# interface_gate.net
KiCad netlist of a schematic drawn in EAGLE
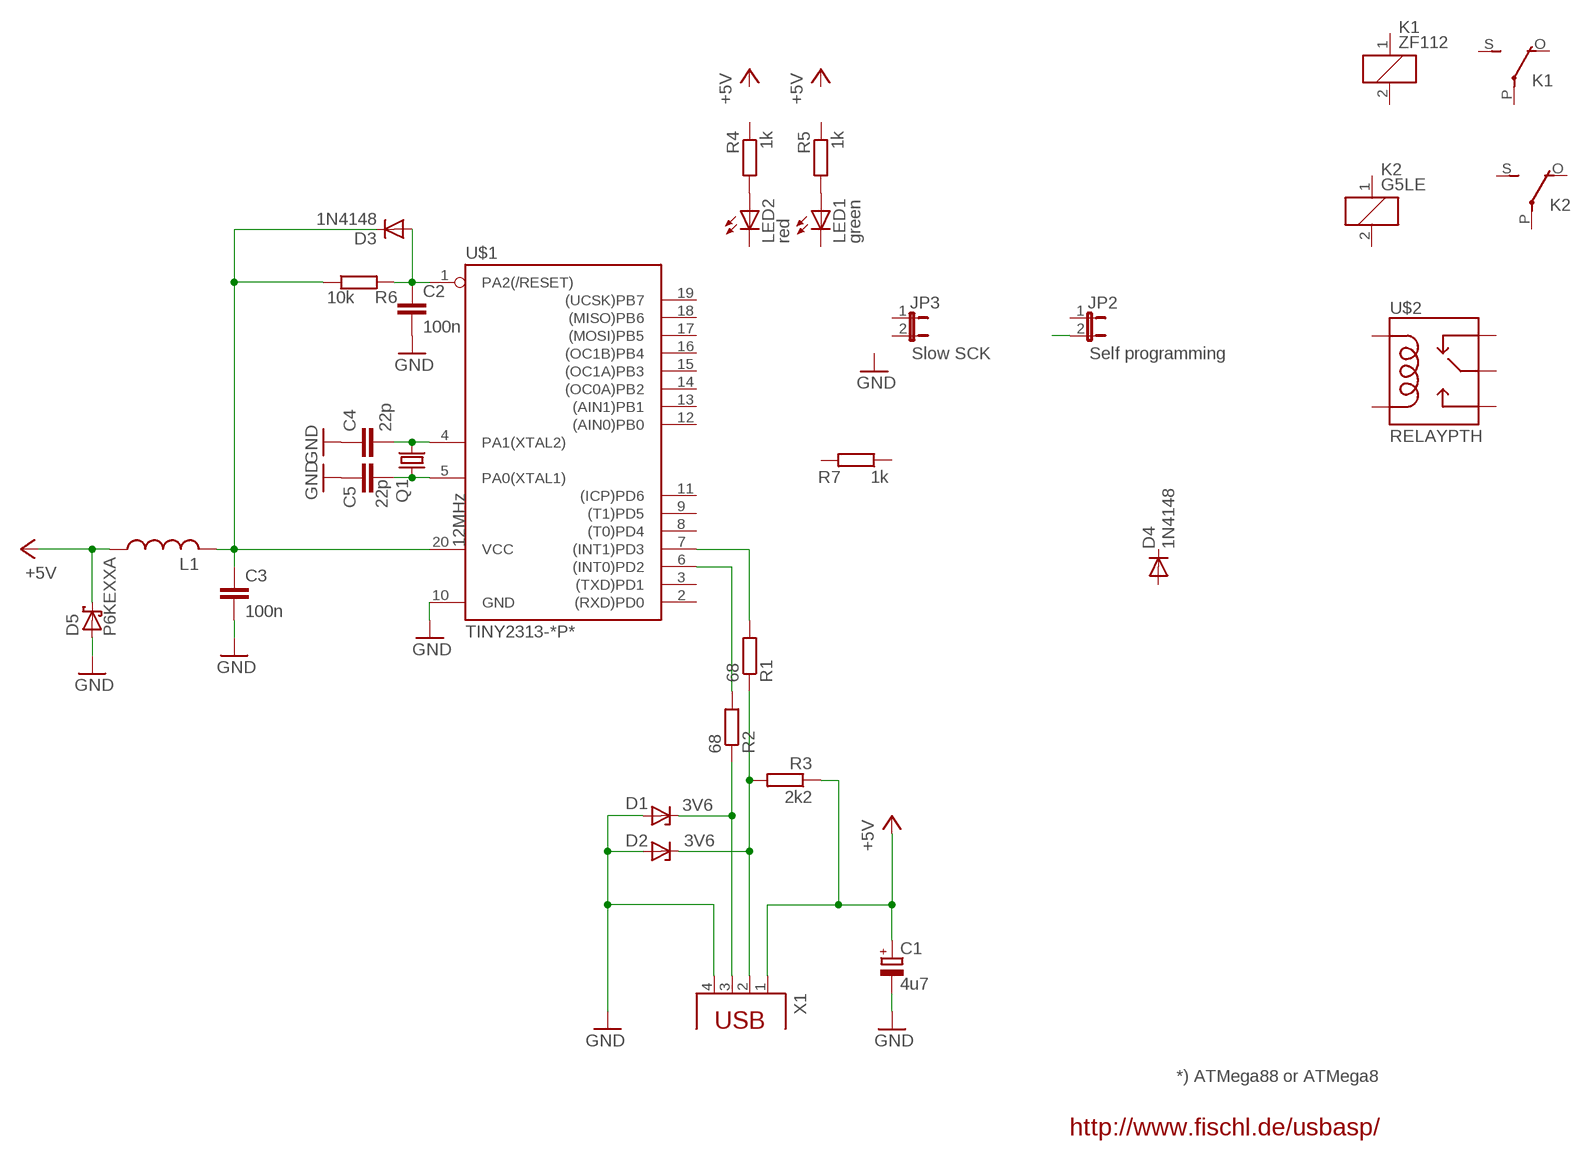
[diagram p0: schematic, sheet 1]

(export (version "E")
  (design (tool "Eeschema 10.0.6"))
  (components
    (comp (ref "C1")
      (value "4u7")
      (footprint "eagle-import:E2,5-5")
      (libsource (lib "eagle-import") (part "CPOL-EUE2.5-5"))
    )
    (comp (ref "C2")
      (value "100n")
      (footprint "eagle-import:C025-024X044")
      (libsource (lib "eagle-import") (part "C-EU025-024X044"))
    )
    (comp (ref "C3")
      (value "100n")
      (footprint "eagle-import:C025-024X044")
      (libsource (lib "eagle-import") (part "C-EU025-024X044"))
    )
    (comp (ref "C4")
      (value "22p")
      (footprint "eagle-import:C025-024X044")
      (libsource (lib "eagle-import") (part "C-EU025-024X044"))
    )
    (comp (ref "C5")
      (value "22p")
      (footprint "eagle-import:C025-024X044")
      (libsource (lib "eagle-import") (part "C-EU025-024X044"))
    )
    (comp (ref "D1")
      (value "3V6")
      (footprint "eagle-import:DO34Z7")
      (libsource (lib "eagle-import") (part "ZENER-DIODEDO34-7"))
    )
    (comp (ref "D2")
      (value "3V6")
      (footprint "eagle-import:DO34Z7")
      (libsource (lib "eagle-import") (part "ZENER-DIODEDO34-7"))
    )
    (comp (ref "D3")
      (value "1N4148")
      (footprint "eagle-import:DO35-10")
      (libsource (lib "eagle-import") (part "1N4148DO35-10"))
    )
    (comp (ref "D4")
      (value "1N4148")
      (footprint "eagle-import:DO35-10")
      (libsource (lib "eagle-import") (part "1N4148DO35-10"))
    )
    (comp (ref "D5")
      (value "P6KEXXA")
      (footprint "eagle-import:C1702-15")
      (libsource (lib "eagle-import") (part "P6KEXXA"))
    )
    (comp (ref "JP2")
      (value "Self programming")
      (footprint "eagle-import:JP1")
      (libsource (lib "eagle-import") (part "JP1E"))
    )
    (comp (ref "JP3")
      (value "Slow SCK")
      (footprint "eagle-import:JP1")
      (libsource (lib "eagle-import") (part "JP1E"))
    )
    (comp (ref "K1")
      (value "ZF112")
      (footprint "eagle-import:ZF112")
      (libsource (lib "eagle-import") (part "ZF112"))
    )
    (comp (ref "K2")
      (value "G5LE")
      (footprint "eagle-import:G5LE")
      (libsource (lib "eagle-import") (part "G5LE"))
    )
    (comp (ref "L1")
      (value "L-US0207/10")
      (footprint "eagle-import:0207_10")
      (libsource (lib "eagle-import") (part "L-US0207/10"))
    )
    (comp (ref "LED1")
      (value "green")
      (footprint "eagle-import:LED3MM")
      (libsource (lib "eagle-import") (part "LED3MM"))
    )
    (comp (ref "LED2")
      (value "red")
      (footprint "eagle-import:LED3MM")
      (libsource (lib "eagle-import") (part "LED3MM"))
    )
    (comp (ref "Q1")
      (value "12MHz")
      (footprint "eagle-import:HC49_S")
      (libsource (lib "eagle-import") (part "CRYTALHC49S"))
    )
    (comp (ref "R1")
      (value "68")
      (footprint "eagle-import:0207_10")
      (libsource (lib "eagle-import") (part "R-EU_0207/10"))
    )
    (comp (ref "R2")
      (value "68")
      (footprint "eagle-import:0207_10")
      (libsource (lib "eagle-import") (part "R-EU_0207/10"))
    )
    (comp (ref "R3")
      (value "2k2")
      (footprint "eagle-import:0207_10")
      (libsource (lib "eagle-import") (part "R-EU_0207/10"))
    )
    (comp (ref "R4")
      (value "1k")
      (footprint "eagle-import:0207_10")
      (libsource (lib "eagle-import") (part "R-EU_0207/10"))
    )
    (comp (ref "R5")
      (value "1k")
      (footprint "eagle-import:0207_10")
      (libsource (lib "eagle-import") (part "R-EU_0207/10"))
    )
    (comp (ref "R6")
      (value "10k")
      (footprint "eagle-import:0207_10")
      (libsource (lib "eagle-import") (part "R-EU_0207/10"))
    )
    (comp (ref "R7")
      (value "1k")
      (footprint "eagle-import:0207_10")
      (libsource (lib "eagle-import") (part "R-EU_0207/10"))
    )
    (comp (ref "U$1")
      (value "TINY2313-*P*")
      (footprint "eagle-import:DIL20")
      (libsource (lib "eagle-import") (part "TINY2313-P"))
    )
    (comp (ref "U$2")
      (value "RELAYPTH")
      (footprint "eagle-import:SRD-05VDC-SL-C")
      (libsource (lib "eagle-import") (part "RELAYPTH"))
    )
    (comp (ref "X1")
      (value "PN61729")
      (footprint "eagle-import:PN61729")
      (libsource (lib "eagle-import") (part "PN61729"))
    )
  )
  (nets
    (net (code "1") (name "+5V") (class "Default")
      (node (ref "C1") (pin "+") (pinfunction "+_+") (pintype "passive"))
      (node (ref "D5") (pin "C") (pinfunction "C_C") (pintype "passive"))
      (node (ref "L1") (pin "1") (pinfunction "1_1") (pintype "passive"))
      (node (ref "R3") (pin "1") (pinfunction "1_1") (pintype "passive"))
      (node (ref "X1") (pin "1") (pinfunction "1_1") (pintype "bidirectional"))
    )
    (net (code "2") (name "GND") (class "Default")
      (node (ref "C1") (pin "-") (pinfunction "-_-") (pintype "passive"))
      (node (ref "C2") (pin "2") (pinfunction "2_2") (pintype "passive"))
      (node (ref "C3") (pin "2") (pinfunction "2_2") (pintype "passive"))
      (node (ref "C4") (pin "1") (pinfunction "1_1") (pintype "passive"))
      (node (ref "C5") (pin "1") (pinfunction "1_1") (pintype "passive"))
      (node (ref "D1") (pin "A") (pinfunction "A_A") (pintype "passive"))
      (node (ref "D2") (pin "A") (pinfunction "A_A") (pintype "passive"))
      (node (ref "D5") (pin "A") (pinfunction "A_A") (pintype "passive"))
      (node (ref "U$1") (pin "10") (pinfunction "GND_10") (pintype "power_in"))
      (node (ref "X1") (pin "4") (pinfunction "4_4") (pintype "bidirectional"))
    )
    (net (code "3") (name "Net-(D1-PadC)") (class "Default")
      (node (ref "D1") (pin "C") (pinfunction "C_C") (pintype "passive"))
      (node (ref "R2") (pin "1") (pinfunction "1_1") (pintype "passive"))
      (node (ref "X1") (pin "3") (pinfunction "3_3") (pintype "bidirectional"))
    )
    (net (code "4") (name "Net-(D2-PadC)") (class "Default")
      (node (ref "D2") (pin "C") (pinfunction "C_C") (pintype "passive"))
      (node (ref "R1") (pin "1") (pinfunction "1_1") (pintype "passive"))
      (node (ref "R3") (pin "2") (pinfunction "2_2") (pintype "passive"))
      (node (ref "X1") (pin "2") (pinfunction "2_2") (pintype "bidirectional"))
    )
    (net (code "5") (name "Net-(LED1-PadA)") (class "Default")
      (node (ref "LED1") (pin "A") (pinfunction "A_A") (pintype "passive"))
      (node (ref "R5") (pin "2") (pinfunction "2_2") (pintype "passive"))
    )
    (net (code "6") (name "Net-(LED2-PadA)") (class "Default")
      (node (ref "LED2") (pin "A") (pinfunction "A_A") (pintype "passive"))
      (node (ref "R4") (pin "2") (pinfunction "2_2") (pintype "passive"))
    )
    (net (code "7") (name "Net-(U$1-(INT0)PD2)") (class "Default")
      (node (ref "R2") (pin "2") (pinfunction "2_2") (pintype "passive"))
      (node (ref "U$1") (pin "6") (pinfunction "(INT0)PD2_6") (pintype "bidirectional"))
    )
    (net (code "8") (name "Net-(U$1-(INT1)PD3)") (class "Default")
      (node (ref "R1") (pin "2") (pinfunction "2_2") (pintype "passive"))
      (node (ref "U$1") (pin "7") (pinfunction "(INT1)PD3_7") (pintype "bidirectional"))
    )
    (net (code "9") (name "Net-(U$1-PA0(XTAL1))") (class "Default")
      (node (ref "C5") (pin "2") (pinfunction "2_2") (pintype "passive"))
      (node (ref "Q1") (pin "1") (pinfunction "1_1") (pintype "passive"))
      (node (ref "U$1") (pin "5") (pinfunction "PA0(XTAL1)_5") (pintype "bidirectional"))
    )
    (net (code "10") (name "Net-(U$1-PA1(XTAL2))") (class "Default")
      (node (ref "C4") (pin "2") (pinfunction "2_2") (pintype "passive"))
      (node (ref "Q1") (pin "2") (pinfunction "2_2") (pintype "passive"))
      (node (ref "U$1") (pin "4") (pinfunction "PA1(XTAL2)_4") (pintype "bidirectional"))
    )
    (net (code "11") (name "Net-(U$1-PA2({slash}RESET))") (class "Default")
      (node (ref "C2") (pin "1") (pinfunction "1_1") (pintype "passive"))
      (node (ref "D3") (pin "A") (pinfunction "A_A") (pintype "passive"))
      (node (ref "R6") (pin "2") (pinfunction "2_2") (pintype "passive"))
      (node (ref "U$1") (pin "1") (pinfunction "PA2(/RESET)_1") (pintype "input"))
    )
    (net (code "12") (name "Net-(U$1-VCC)") (class "Default")
      (node (ref "C3") (pin "1") (pinfunction "1_1") (pintype "passive"))
      (node (ref "D3") (pin "C") (pinfunction "C_C") (pintype "passive"))
      (node (ref "L1") (pin "2") (pinfunction "2_2") (pintype "passive"))
      (node (ref "R6") (pin "1") (pinfunction "1_1") (pintype "passive"))
      (node (ref "U$1") (pin "20") (pinfunction "VCC_20") (pintype "power_in"))
    )
    (net (code "13") (name "unconnected-(D4-PadA)") (class "Default")
      (node (ref "D4") (pin "A") (pinfunction "A_A") (pintype "passive"))
    )
    (net (code "14") (name "unconnected-(D4-PadC)") (class "Default")
      (node (ref "D4") (pin "C") (pinfunction "C_C") (pintype "passive"))
    )
    (net (code "15") (name "unconnected-(JP2-Pad1)") (class "Default")
      (node (ref "JP2") (pin "1") (pinfunction "1_1") (pintype "passive"))
    )
    (net (code "16") (name "unconnected-(JP2-Pad2)") (class "Default")
      (node (ref "JP2") (pin "2") (pinfunction "2_2") (pintype "passive"))
    )
    (net (code "17") (name "unconnected-(JP3-Pad1)") (class "Default")
      (node (ref "JP3") (pin "1") (pinfunction "1_1") (pintype "passive"))
    )
    (net (code "18") (name "unconnected-(JP3-Pad2)") (class "Default")
      (node (ref "JP3") (pin "2") (pinfunction "2_2") (pintype "passive"))
    )
    (net (code "19") (name "unconnected-(K1-Pad1)") (class "Default")
      (node (ref "K1") (pin "1") (pinfunction "1_1") (pintype "passive"))
    )
    (net (code "20") (name "unconnected-(K1-Pad2)") (class "Default")
      (node (ref "K1") (pin "2") (pinfunction "2_2") (pintype "passive"))
    )
    (net (code "21") (name "unconnected-(K1-PadO)") (class "Default")
      (node (ref "K1") (pin "O") (pinfunction "O_O") (pintype "passive"))
    )
    (net (code "22") (name "unconnected-(K1-PadP)") (class "Default")
      (node (ref "K1") (pin "P") (pinfunction "P_P") (pintype "passive"))
    )
    (net (code "23") (name "unconnected-(K1-PadS)") (class "Default")
      (node (ref "K1") (pin "S") (pinfunction "S_S") (pintype "passive"))
    )
    (net (code "24") (name "unconnected-(K2-Pad1)") (class "Default")
      (node (ref "K2") (pin "1") (pinfunction "1_1") (pintype "passive"))
    )
    (net (code "25") (name "unconnected-(K2-Pad2)") (class "Default")
      (node (ref "K2") (pin "2") (pinfunction "2_2") (pintype "passive"))
    )
    (net (code "26") (name "unconnected-(K2-PadO)") (class "Default")
      (node (ref "K2") (pin "O") (pinfunction "O_O") (pintype "passive"))
    )
    (net (code "27") (name "unconnected-(K2-PadP)") (class "Default")
      (node (ref "K2") (pin "P") (pinfunction "P_P") (pintype "passive"))
    )
    (net (code "28") (name "unconnected-(K2-PadS)") (class "Default")
      (node (ref "K2") (pin "S") (pinfunction "S_S") (pintype "passive"))
    )
    (net (code "29") (name "unconnected-(LED1-C-PadK)") (class "Default")
      (node (ref "LED1") (pin "K") (pinfunction "C_K") (pintype "passive"))
    )
    (net (code "30") (name "unconnected-(LED2-C-PadK)") (class "Default")
      (node (ref "LED2") (pin "K") (pinfunction "C_K") (pintype "passive"))
    )
    (net (code "31") (name "unconnected-(R4-Pad1)") (class "Default")
      (node (ref "R4") (pin "1") (pinfunction "1_1") (pintype "passive"))
    )
    (net (code "32") (name "unconnected-(R5-Pad1)") (class "Default")
      (node (ref "R5") (pin "1") (pinfunction "1_1") (pintype "passive"))
    )
    (net (code "33") (name "unconnected-(R7-Pad1)") (class "Default")
      (node (ref "R7") (pin "1") (pinfunction "1_1") (pintype "passive"))
    )
    (net (code "34") (name "unconnected-(R7-Pad2)") (class "Default")
      (node (ref "R7") (pin "2") (pinfunction "2_2") (pintype "passive"))
    )
    (net (code "35") (name "unconnected-(U$1-(AIN0)PB0-Pad12)") (class "Default")
      (node (ref "U$1") (pin "12") (pinfunction "(AIN0)PB0_12") (pintype "bidirectional"))
    )
    (net (code "36") (name "unconnected-(U$1-(AIN1)PB1-Pad13)") (class "Default")
      (node (ref "U$1") (pin "13") (pinfunction "(AIN1)PB1_13") (pintype "bidirectional"))
    )
    (net (code "37") (name "unconnected-(U$1-(ICP)PD6-Pad11)") (class "Default")
      (node (ref "U$1") (pin "11") (pinfunction "(ICP)PD6_11") (pintype "bidirectional"))
    )
    (net (code "38") (name "unconnected-(U$1-(MISO)PB6-Pad18)") (class "Default")
      (node (ref "U$1") (pin "18") (pinfunction "(MISO)PB6_18") (pintype "bidirectional"))
    )
    (net (code "39") (name "unconnected-(U$1-(MOSI)PB5-Pad17)") (class "Default")
      (node (ref "U$1") (pin "17") (pinfunction "(MOSI)PB5_17") (pintype "bidirectional"))
    )
    (net (code "40") (name "unconnected-(U$1-(OC0A)PB2-Pad14)") (class "Default")
      (node (ref "U$1") (pin "14") (pinfunction "(OC0A)PB2_14") (pintype "bidirectional"))
    )
    (net (code "41") (name "unconnected-(U$1-(OC1A)PB3-Pad15)") (class "Default")
      (node (ref "U$1") (pin "15") (pinfunction "(OC1A)PB3_15") (pintype "bidirectional"))
    )
    (net (code "42") (name "unconnected-(U$1-(OC1B)PB4-Pad16)") (class "Default")
      (node (ref "U$1") (pin "16") (pinfunction "(OC1B)PB4_16") (pintype "bidirectional"))
    )
    (net (code "43") (name "unconnected-(U$1-(RXD)PD0-Pad2)") (class "Default")
      (node (ref "U$1") (pin "2") (pinfunction "(RXD)PD0_2") (pintype "bidirectional"))
    )
    (net (code "44") (name "unconnected-(U$1-(T0)PD4-Pad8)") (class "Default")
      (node (ref "U$1") (pin "8") (pinfunction "(T0)PD4_8") (pintype "bidirectional"))
    )
    (net (code "45") (name "unconnected-(U$1-(T1)PD5-Pad9)") (class "Default")
      (node (ref "U$1") (pin "9") (pinfunction "(T1)PD5_9") (pintype "bidirectional"))
    )
    (net (code "46") (name "unconnected-(U$1-(TXD)PD1-Pad3)") (class "Default")
      (node (ref "U$1") (pin "3") (pinfunction "(TXD)PD1_3") (pintype "bidirectional"))
    )
    (net (code "47") (name "unconnected-(U$1-(UCSK)PB7-Pad19)") (class "Default")
      (node (ref "U$1") (pin "19") (pinfunction "(UCSK)PB7_19") (pintype "bidirectional"))
    )
    (net (code "48") (name "unconnected-(U$2-PadCOIL0)") (class "Default")
      (node (ref "U$2") (pin "COIL0") (pinfunction "COIL0_COIL0") (pintype "bidirectional"))
    )
    (net (code "49") (name "unconnected-(U$2-PadCOIL1)") (class "Default")
      (node (ref "U$2") (pin "COIL1") (pinfunction "COIL1_COIL1") (pintype "bidirectional"))
    )
    (net (code "50") (name "unconnected-(U$2-PadSWCOMMON)") (class "Default")
      (node (ref "U$2") (pin "SWCOMMON") (pinfunction "SWCOMMON_SWCOMMON") (pintype "bidirectional"))
    )
    (net (code "51") (name "unconnected-(U$2-PadSWOPEN)") (class "Default")
      (node (ref "U$2") (pin "SWOPEN") (pinfunction "SWOPEN_SWOPEN") (pintype "bidirectional"))
    )
    (net (code "52") (name "unconnected-(U$2-SWCLOSE-PadSWCLOSED)") (class "Default")
      (node (ref "U$2") (pin "SWCLOSED") (pinfunction "SWCLOSE_SWCLOSED") (pintype "bidirectional"))
    )
  )
)
